# Pads.net
KiCad netlist of a schematic drawn in Altium Designer
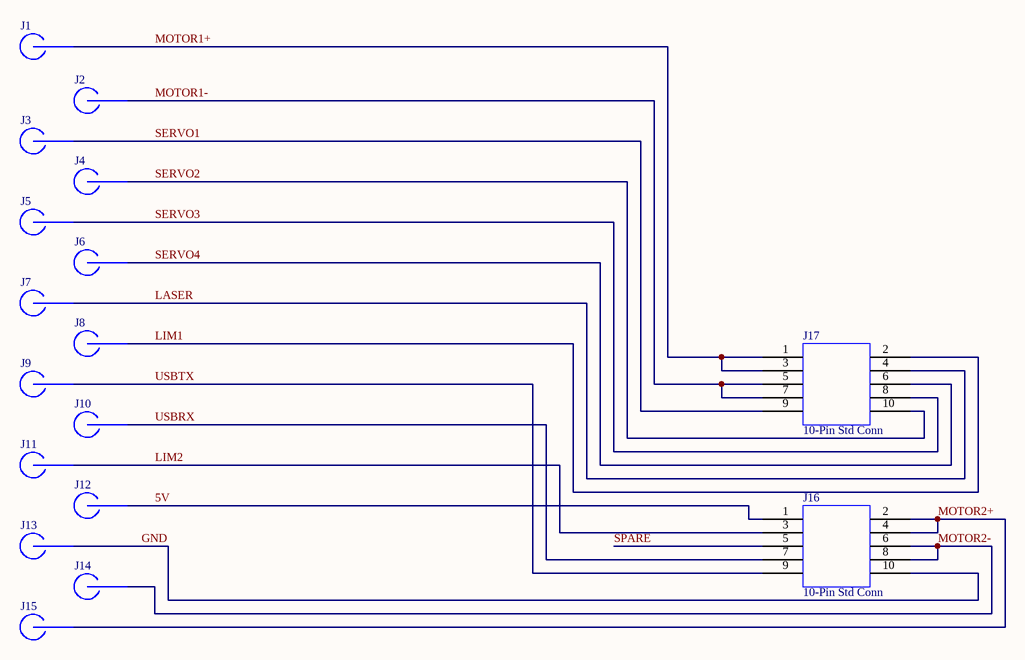
[diagram p0: Pads.SchDoc]

(export (version "E")
  (design (tool "Eeschema 10.0.6"))
  (components
    (comp (ref "J1")
      (value "PogoPinPad")
      (libsource (lib "Husky Robotics Standard Library 2019-2020") (part "PogoPinPad"))
    )
    (comp (ref "J2")
      (value "PogoPinPad")
      (libsource (lib "Husky Robotics Standard Library 2019-2020") (part "PogoPinPad"))
    )
    (comp (ref "J3")
      (value "PogoPinPad")
      (libsource (lib "Husky Robotics Standard Library 2019-2020") (part "PogoPinPad"))
    )
    (comp (ref "J4")
      (value "PogoPinPad")
      (libsource (lib "Husky Robotics Standard Library 2019-2020") (part "PogoPinPad"))
    )
    (comp (ref "J5")
      (value "PogoPinPad")
      (libsource (lib "Husky Robotics Standard Library 2019-2020") (part "PogoPinPad"))
    )
    (comp (ref "J6")
      (value "PogoPinPad")
      (libsource (lib "Husky Robotics Standard Library 2019-2020") (part "PogoPinPad"))
    )
    (comp (ref "J7")
      (value "PogoPinPad")
      (libsource (lib "Husky Robotics Standard Library 2019-2020") (part "PogoPinPad"))
    )
    (comp (ref "J8")
      (value "PogoPinPad")
      (libsource (lib "Husky Robotics Standard Library 2019-2020") (part "PogoPinPad"))
    )
    (comp (ref "J9")
      (value "PogoPinPad")
      (libsource (lib "Husky Robotics Standard Library 2019-2020") (part "PogoPinPad"))
    )
    (comp (ref "J10")
      (value "PogoPinPad")
      (libsource (lib "Husky Robotics Standard Library 2019-2020") (part "PogoPinPad"))
    )
    (comp (ref "J11")
      (value "PogoPinPad")
      (libsource (lib "Husky Robotics Standard Library 2019-2020") (part "PogoPinPad"))
    )
    (comp (ref "J12")
      (value "PogoPinPad")
      (libsource (lib "Husky Robotics Standard Library 2019-2020") (part "PogoPinPad"))
    )
    (comp (ref "J13")
      (value "PogoPinPad")
      (libsource (lib "Husky Robotics Standard Library 2019-2020") (part "PogoPinPad"))
    )
    (comp (ref "J14")
      (value "PogoPinPad")
      (libsource (lib "Husky Robotics Standard Library 2019-2020") (part "PogoPinPad"))
    )
    (comp (ref "J15")
      (value "PogoPinPad")
      (libsource (lib "Husky Robotics Standard Library 2019-2020") (part "PogoPinPad"))
    )
    (comp (ref "J16")
      (value "10-Pin Std Conn")
      (footprint "PogoPinPadSide:FTSH-105-01-F-DV")
      (libsource (lib "Husky Robotics Standard Library 2019-2020") (part "10-Pin Std Conn"))
    )
    (comp (ref "J17")
      (value "10-Pin Std Conn")
      (footprint "PogoPinPadSide:FTSH-105-01-F-DV")
      (libsource (lib "Husky Robotics Standard Library 2019-2020") (part "10-Pin Std Conn"))
    )
  )
  (nets
    (net (code "1") (name "/5V") (class "Default")
      (node (ref "J12") (pin "1") (pinfunction "Pin_1") (pintype "passive"))
      (node (ref "J16") (pin "1") (pinfunction "Pin_1") (pintype "passive"))
    )
    (net (code "2") (name "/GND") (class "Default")
      (node (ref "J13") (pin "1") (pinfunction "Pin_1") (pintype "passive"))
      (node (ref "J16") (pin "10") (pinfunction "Pin_10") (pintype "passive"))
    )
    (net (code "3") (name "/LASER") (class "Default")
      (node (ref "J17") (pin "4") (pinfunction "Pin_4") (pintype "passive"))
      (node (ref "J7") (pin "1") (pinfunction "Pin_1") (pintype "passive"))
    )
    (net (code "4") (name "/LIM1") (class "Default")
      (node (ref "J17") (pin "2") (pinfunction "Pin_2") (pintype "passive"))
      (node (ref "J8") (pin "1") (pinfunction "Pin_1") (pintype "passive"))
    )
    (net (code "5") (name "/LIM2") (class "Default")
      (node (ref "J11") (pin "1") (pinfunction "Pin_1") (pintype "passive"))
      (node (ref "J16") (pin "3") (pinfunction "Pin_3") (pintype "passive"))
    )
    (net (code "6") (name "/MOTOR1+") (class "Default")
      (node (ref "J1") (pin "1") (pinfunction "Pin_1") (pintype "passive"))
      (node (ref "J17") (pin "1") (pinfunction "Pin_1") (pintype "passive"))
      (node (ref "J17") (pin "3") (pinfunction "Pin_3") (pintype "passive"))
    )
    (net (code "7") (name "/MOTOR1-") (class "Default")
      (node (ref "J17") (pin "5") (pinfunction "Pin_5") (pintype "passive"))
      (node (ref "J17") (pin "7") (pinfunction "Pin_7") (pintype "passive"))
      (node (ref "J2") (pin "1") (pinfunction "Pin_1") (pintype "passive"))
    )
    (net (code "8") (name "/MOTOR2+") (class "Default")
      (node (ref "J15") (pin "1") (pinfunction "Pin_1") (pintype "passive"))
      (node (ref "J16") (pin "2") (pinfunction "Pin_2") (pintype "passive"))
      (node (ref "J16") (pin "4") (pinfunction "Pin_4") (pintype "passive"))
    )
    (net (code "9") (name "/MOTOR2-") (class "Default")
      (node (ref "J14") (pin "1") (pinfunction "Pin_1") (pintype "passive"))
      (node (ref "J16") (pin "6") (pinfunction "Pin_6") (pintype "passive"))
      (node (ref "J16") (pin "8") (pinfunction "Pin_8") (pintype "passive"))
    )
    (net (code "10") (name "/SERVO1") (class "Default")
      (node (ref "J17") (pin "9") (pinfunction "Pin_9") (pintype "passive"))
      (node (ref "J3") (pin "1") (pinfunction "Pin_1") (pintype "passive"))
    )
    (net (code "11") (name "/SERVO2") (class "Default")
      (node (ref "J17") (pin "10") (pinfunction "Pin_10") (pintype "passive"))
      (node (ref "J4") (pin "1") (pinfunction "Pin_1") (pintype "passive"))
    )
    (net (code "12") (name "/SERVO3") (class "Default")
      (node (ref "J17") (pin "8") (pinfunction "Pin_8") (pintype "passive"))
      (node (ref "J5") (pin "1") (pinfunction "Pin_1") (pintype "passive"))
    )
    (net (code "13") (name "/SERVO4") (class "Default")
      (node (ref "J17") (pin "6") (pinfunction "Pin_6") (pintype "passive"))
      (node (ref "J6") (pin "1") (pinfunction "Pin_1") (pintype "passive"))
    )
    (net (code "14") (name "/SPARE") (class "Default")
      (node (ref "J16") (pin "5") (pinfunction "Pin_5") (pintype "passive"))
    )
    (net (code "15") (name "/USBRX") (class "Default")
      (node (ref "J10") (pin "1") (pinfunction "Pin_1") (pintype "passive"))
      (node (ref "J16") (pin "7") (pinfunction "Pin_7") (pintype "passive"))
    )
    (net (code "16") (name "/USBTX") (class "Default")
      (node (ref "J16") (pin "9") (pinfunction "Pin_9") (pintype "passive"))
      (node (ref "J9") (pin "1") (pinfunction "Pin_1") (pintype "passive"))
    )
  )
)
